# Sitara_Connectors.net
KiCad netlist of a schematic drawn in Altium Designer
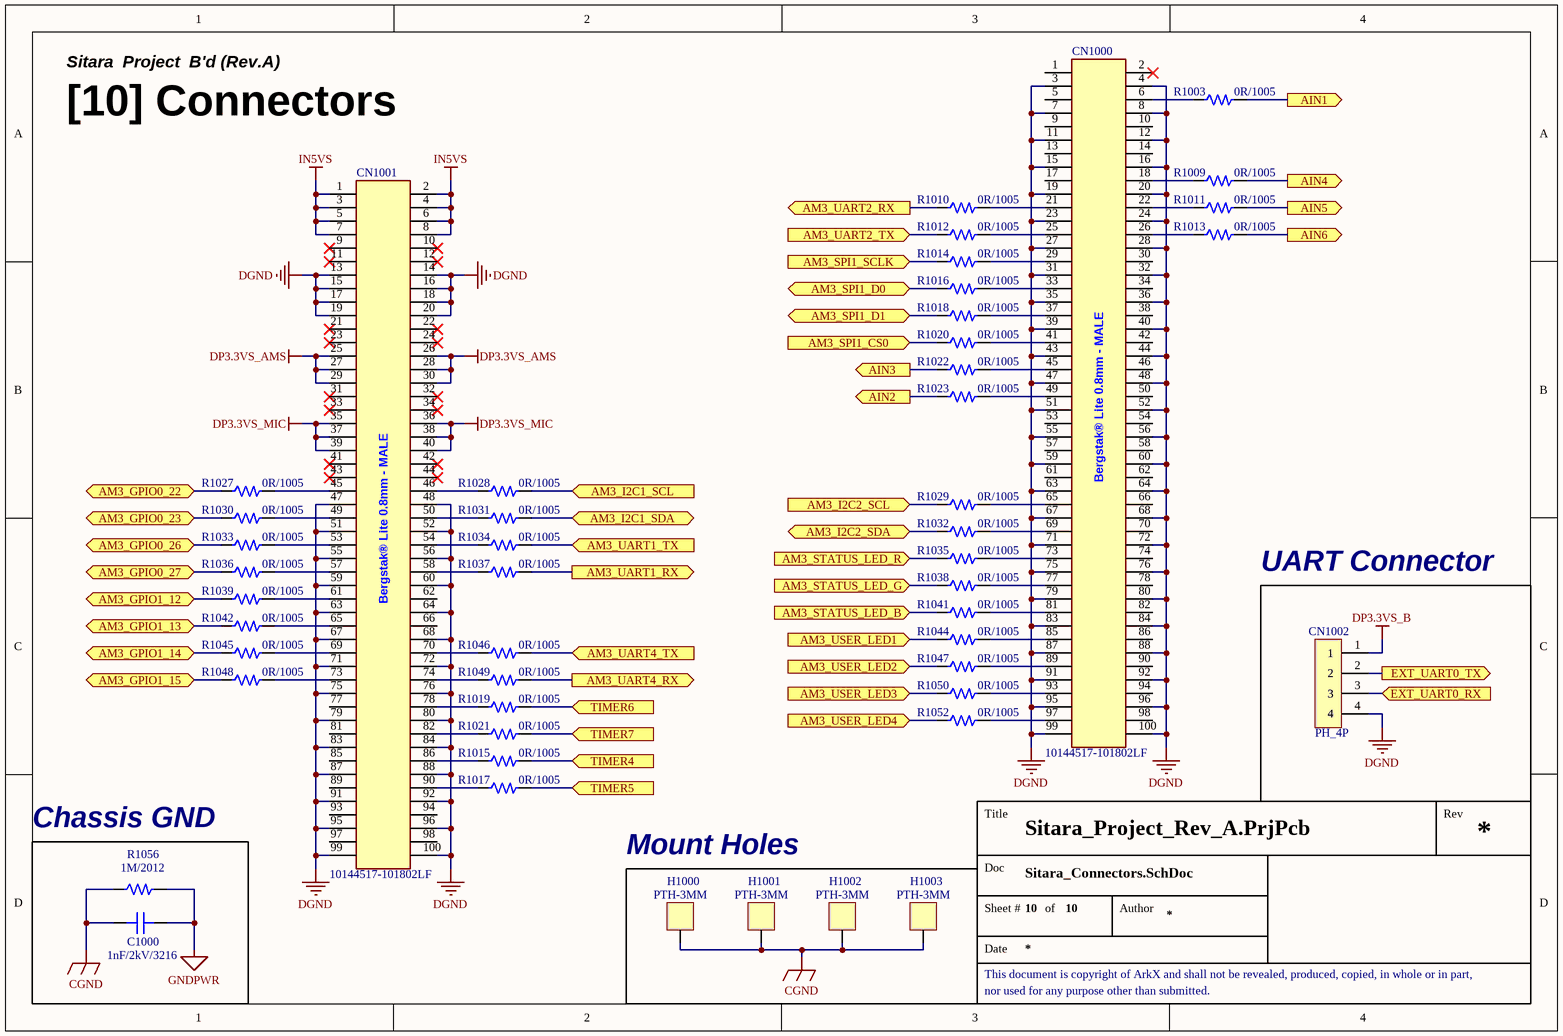
[diagram p0: Sitara_Connectors.SchDoc]

(export (version "E")
  (design (tool "Eeschema 10.0.6"))
  (components
    (comp (ref "C1000")
      (value "1nF/2kV/3216")
      (footprint "CAP 3216 (1206_INCH) - H1.8MM")
      (description "Ceramic CAP_1nF/2kV/3216")
      (fields (field (name "LCSC PART #") "C9196"))
      (libsource (lib "Arkx") (part "CAP_1nF/2kV/3216"))
    )
    (comp (ref "CN1000")
      (value "10144517-101802LF")
      (footprint "CON_BergStak-Lite(0.8mm)_MALE-100P(10144517-101802LF)_HandSolder")
      (libsource (lib "Arkx") (part "CON_BergStak-Lite(0.8mm)_MALE-100P(10144517-101802LF)"))
    )
    (comp (ref "CN1001")
      (value "10144517-101802LF")
      (footprint "CON_BergStak-Lite(0.8mm)_MALE-100P(10144517-101802LF)_HandSolder")
      (libsource (lib "Arkx") (part "CON_BergStak-Lite(0.8mm)_MALE-100P(10144517-101802LF)"))
    )
    (comp (ref "CN1002")
      (value "PH_4P")
      (footprint "CON PIN_HEADER-4PIN(2.54MM)")
      (description "CON_PIN_HEADER_SINGLE-4PIN(2.54MM)")
      (libsource (lib "Arkx") (part "CON_PIN_HEADER_SINGLE-4PIN(2.54MM)"))
    )
    (comp (ref "H1000")
      (value "PTH-3MM")
      (footprint "HOLE PTH-3MM")
      (description "Plated-Through Hole 3mm")
      (libsource (lib "Arkx") (part "HOLE_PTH-3.0MM"))
    )
    (comp (ref "H1001")
      (value "PTH-3MM")
      (footprint "HOLE PTH-3MM")
      (description "Plated-Through Hole 3mm")
      (libsource (lib "Arkx") (part "HOLE_PTH-3.0MM"))
    )
    (comp (ref "H1002")
      (value "PTH-3MM")
      (footprint "HOLE PTH-3MM")
      (description "Plated-Through Hole 3mm")
      (libsource (lib "Arkx") (part "HOLE_PTH-3.0MM"))
    )
    (comp (ref "H1003")
      (value "PTH-3MM")
      (footprint "HOLE PTH-3MM")
      (description "Plated-Through Hole 3mm")
      (libsource (lib "Arkx") (part "HOLE_PTH-3.0MM"))
    )
    (comp (ref "R1003")
      (value "0R/1005")
      (footprint "RES 1005 (0402_inch)")
      (description "RES_0R/1005/62.5mW")
      (fields (field (name "LCSC PART #") "C17168"))
      (libsource (lib "Arkx") (part "RES_0R/1005/62.5mW"))
    )
    (comp (ref "R1009")
      (value "0R/1005")
      (footprint "RES 1005 (0402_inch)")
      (description "RES_0R/1005/62.5mW")
      (fields (field (name "LCSC PART #") "C17168"))
      (libsource (lib "Arkx") (part "RES_0R/1005/62.5mW"))
    )
    (comp (ref "R1010")
      (value "0R/1005")
      (footprint "RES 1005 (0402_inch)")
      (description "RES_0R/1005/62.5mW")
      (fields (field (name "LCSC PART #") "C17168"))
      (libsource (lib "Arkx") (part "RES_0R/1005/62.5mW"))
    )
    (comp (ref "R1011")
      (value "0R/1005")
      (footprint "RES 1005 (0402_inch)")
      (description "RES_0R/1005/62.5mW")
      (fields (field (name "LCSC PART #") "C17168"))
      (libsource (lib "Arkx") (part "RES_0R/1005/62.5mW"))
    )
    (comp (ref "R1012")
      (value "0R/1005")
      (footprint "RES 1005 (0402_inch)")
      (description "RES_0R/1005/62.5mW")
      (fields (field (name "LCSC PART #") "C17168"))
      (libsource (lib "Arkx") (part "RES_0R/1005/62.5mW"))
    )
    (comp (ref "R1013")
      (value "0R/1005")
      (footprint "RES 1005 (0402_inch)")
      (description "RES_0R/1005/62.5mW")
      (fields (field (name "LCSC PART #") "C17168"))
      (libsource (lib "Arkx") (part "RES_0R/1005/62.5mW"))
    )
    (comp (ref "R1014")
      (value "0R/1005")
      (footprint "RES 1005 (0402_inch)")
      (description "RES_0R/1005/62.5mW")
      (fields (field (name "LCSC PART #") "C17168"))
      (libsource (lib "Arkx") (part "RES_0R/1005/62.5mW"))
    )
    (comp (ref "R1015")
      (value "0R/1005")
      (footprint "RES 1005 (0402_inch)")
      (description "RES_0R/1005/62.5mW")
      (fields (field (name "LCSC PART #") "C17168"))
      (libsource (lib "Arkx") (part "RES_0R/1005/62.5mW"))
    )
    (comp (ref "R1016")
      (value "0R/1005")
      (footprint "RES 1005 (0402_inch)")
      (description "RES_0R/1005/62.5mW")
      (fields (field (name "LCSC PART #") "C17168"))
      (libsource (lib "Arkx") (part "RES_0R/1005/62.5mW"))
    )
    (comp (ref "R1017")
      (value "0R/1005")
      (footprint "RES 1005 (0402_inch)")
      (description "RES_0R/1005/62.5mW")
      (fields (field (name "LCSC PART #") "C17168"))
      (libsource (lib "Arkx") (part "RES_0R/1005/62.5mW"))
    )
    (comp (ref "R1018")
      (value "0R/1005")
      (footprint "RES 1005 (0402_inch)")
      (description "RES_0R/1005/62.5mW")
      (fields (field (name "LCSC PART #") "C17168"))
      (libsource (lib "Arkx") (part "RES_0R/1005/62.5mW"))
    )
    (comp (ref "R1019")
      (value "0R/1005")
      (footprint "RES 1005 (0402_inch)")
      (description "RES_0R/1005/62.5mW")
      (fields (field (name "LCSC PART #") "C17168"))
      (libsource (lib "Arkx") (part "RES_0R/1005/62.5mW"))
    )
    (comp (ref "R1020")
      (value "0R/1005")
      (footprint "RES 1005 (0402_inch)")
      (description "RES_0R/1005/62.5mW")
      (fields (field (name "LCSC PART #") "C17168"))
      (libsource (lib "Arkx") (part "RES_0R/1005/62.5mW"))
    )
    (comp (ref "R1021")
      (value "0R/1005")
      (footprint "RES 1005 (0402_inch)")
      (description "RES_0R/1005/62.5mW")
      (fields (field (name "LCSC PART #") "C17168"))
      (libsource (lib "Arkx") (part "RES_0R/1005/62.5mW"))
    )
    (comp (ref "R1022")
      (value "0R/1005")
      (footprint "RES 1005 (0402_inch)")
      (description "RES_0R/1005/62.5mW")
      (fields (field (name "LCSC PART #") "C17168"))
      (libsource (lib "Arkx") (part "RES_0R/1005/62.5mW"))
    )
    (comp (ref "R1023")
      (value "0R/1005")
      (footprint "RES 1005 (0402_inch)")
      (description "RES_0R/1005/62.5mW")
      (fields (field (name "LCSC PART #") "C17168"))
      (libsource (lib "Arkx") (part "RES_0R/1005/62.5mW"))
    )
    (comp (ref "R1027")
      (value "0R/1005")
      (footprint "RES 1005 (0402_inch)")
      (description "RES_0R/1005/62.5mW")
      (fields (field (name "LCSC PART #") "C17168"))
      (libsource (lib "Arkx") (part "RES_0R/1005/62.5mW"))
    )
    (comp (ref "R1028")
      (value "0R/1005")
      (footprint "RES 1005 (0402_inch)")
      (description "RES_0R/1005/62.5mW")
      (fields (field (name "LCSC PART #") "C17168"))
      (libsource (lib "Arkx") (part "RES_0R/1005/62.5mW"))
    )
    (comp (ref "R1029")
      (value "0R/1005")
      (footprint "RES 1005 (0402_inch)")
      (description "RES_0R/1005/62.5mW")
      (fields (field (name "LCSC PART #") "C17168"))
      (libsource (lib "Arkx") (part "RES_0R/1005/62.5mW"))
    )
    (comp (ref "R1030")
      (value "0R/1005")
      (footprint "RES 1005 (0402_inch)")
      (description "RES_0R/1005/62.5mW")
      (fields (field (name "LCSC PART #") "C17168"))
      (libsource (lib "Arkx") (part "RES_0R/1005/62.5mW"))
    )
    (comp (ref "R1031")
      (value "0R/1005")
      (footprint "RES 1005 (0402_inch)")
      (description "RES_0R/1005/62.5mW")
      (fields (field (name "LCSC PART #") "C17168"))
      (libsource (lib "Arkx") (part "RES_0R/1005/62.5mW"))
    )
    (comp (ref "R1032")
      (value "0R/1005")
      (footprint "RES 1005 (0402_inch)")
      (description "RES_0R/1005/62.5mW")
      (fields (field (name "LCSC PART #") "C17168"))
      (libsource (lib "Arkx") (part "RES_0R/1005/62.5mW"))
    )
    (comp (ref "R1033")
      (value "0R/1005")
      (footprint "RES 1005 (0402_inch)")
      (description "RES_0R/1005/62.5mW")
      (fields (field (name "LCSC PART #") "C17168"))
      (libsource (lib "Arkx") (part "RES_0R/1005/62.5mW"))
    )
    (comp (ref "R1034")
      (value "0R/1005")
      (footprint "RES 1005 (0402_inch)")
      (description "RES_0R/1005/62.5mW")
      (fields (field (name "LCSC PART #") "C17168"))
      (libsource (lib "Arkx") (part "RES_0R/1005/62.5mW"))
    )
    (comp (ref "R1035")
      (value "0R/1005")
      (footprint "RES 1005 (0402_inch)")
      (description "RES_0R/1005/62.5mW")
      (fields (field (name "LCSC PART #") "C17168"))
      (libsource (lib "Arkx") (part "RES_0R/1005/62.5mW"))
    )
    (comp (ref "R1036")
      (value "0R/1005")
      (footprint "RES 1005 (0402_inch)")
      (description "RES_0R/1005/62.5mW")
      (fields (field (name "LCSC PART #") "C17168"))
      (libsource (lib "Arkx") (part "RES_0R/1005/62.5mW"))
    )
    (comp (ref "R1037")
      (value "0R/1005")
      (footprint "RES 1005 (0402_inch)")
      (description "RES_0R/1005/62.5mW")
      (fields (field (name "LCSC PART #") "C17168"))
      (libsource (lib "Arkx") (part "RES_0R/1005/62.5mW"))
    )
    (comp (ref "R1038")
      (value "0R/1005")
      (footprint "RES 1005 (0402_inch)")
      (description "RES_0R/1005/62.5mW")
      (fields (field (name "LCSC PART #") "C17168"))
      (libsource (lib "Arkx") (part "RES_0R/1005/62.5mW"))
    )
    (comp (ref "R1039")
      (value "0R/1005")
      (footprint "RES 1005 (0402_inch)")
      (description "RES_0R/1005/62.5mW")
      (fields (field (name "LCSC PART #") "C17168"))
      (libsource (lib "Arkx") (part "RES_0R/1005/62.5mW"))
    )
    (comp (ref "R1041")
      (value "0R/1005")
      (footprint "RES 1005 (0402_inch)")
      (description "RES_0R/1005/62.5mW")
      (fields (field (name "LCSC PART #") "C17168"))
      (libsource (lib "Arkx") (part "RES_0R/1005/62.5mW"))
    )
    (comp (ref "R1042")
      (value "0R/1005")
      (footprint "RES 1005 (0402_inch)")
      (description "RES_0R/1005/62.5mW")
      (fields (field (name "LCSC PART #") "C17168"))
      (libsource (lib "Arkx") (part "RES_0R/1005/62.5mW"))
    )
    (comp (ref "R1044")
      (value "0R/1005")
      (footprint "RES 1005 (0402_inch)")
      (description "RES_0R/1005/62.5mW")
      (fields (field (name "LCSC PART #") "C17168"))
      (libsource (lib "Arkx") (part "RES_0R/1005/62.5mW"))
    )
    (comp (ref "R1045")
      (value "0R/1005")
      (footprint "RES 1005 (0402_inch)")
      (description "RES_0R/1005/62.5mW")
      (fields (field (name "LCSC PART #") "C17168"))
      (libsource (lib "Arkx") (part "RES_0R/1005/62.5mW"))
    )
    (comp (ref "R1046")
      (value "0R/1005")
      (footprint "RES 1005 (0402_inch)")
      (description "RES_0R/1005/62.5mW")
      (fields (field (name "LCSC PART #") "C17168"))
      (libsource (lib "Arkx") (part "RES_0R/1005/62.5mW"))
    )
    (comp (ref "R1047")
      (value "0R/1005")
      (footprint "RES 1005 (0402_inch)")
      (description "RES_0R/1005/62.5mW")
      (fields (field (name "LCSC PART #") "C17168"))
      (libsource (lib "Arkx") (part "RES_0R/1005/62.5mW"))
    )
    (comp (ref "R1048")
      (value "0R/1005")
      (footprint "RES 1005 (0402_inch)")
      (description "RES_0R/1005/62.5mW")
      (fields (field (name "LCSC PART #") "C17168"))
      (libsource (lib "Arkx") (part "RES_0R/1005/62.5mW"))
    )
    (comp (ref "R1049")
      (value "0R/1005")
      (footprint "RES 1005 (0402_inch)")
      (description "RES_0R/1005/62.5mW")
      (fields (field (name "LCSC PART #") "C17168"))
      (libsource (lib "Arkx") (part "RES_0R/1005/62.5mW"))
    )
    (comp (ref "R1050")
      (value "0R/1005")
      (footprint "RES 1005 (0402_inch)")
      (description "RES_0R/1005/62.5mW")
      (fields (field (name "LCSC PART #") "C17168"))
      (libsource (lib "Arkx") (part "RES_0R/1005/62.5mW"))
    )
    (comp (ref "R1052")
      (value "0R/1005")
      (footprint "RES 1005 (0402_inch)")
      (description "RES_0R/1005/62.5mW")
      (fields (field (name "LCSC PART #") "C17168"))
      (libsource (lib "Arkx") (part "RES_0R/1005/62.5mW"))
    )
    (comp (ref "R1056")
      (value "1M/2012")
      (footprint "RES 2012 (0805_inch)")
      (description "RES_1M/2012/0.125W")
      (fields (field (name "LCSC PART #") "C17514"))
      (libsource (lib "Arkx") (part "RES_1M/2012/0.125W"))
    )
  )
  (nets
    (net (code "1") (name "/AIN1") (class "Default")
      (node (ref "R1003") (pin "2") (pinfunction "2_2") (pintype "passive"))
    )
    (net (code "2") (name "/AIN2") (class "Default")
      (node (ref "R1023") (pin "1") (pinfunction "1_1") (pintype "passive"))
    )
    (net (code "3") (name "/AIN3") (class "Default")
      (node (ref "R1022") (pin "1") (pinfunction "1_1") (pintype "passive"))
    )
    (net (code "4") (name "/AIN4") (class "Default")
      (node (ref "R1009") (pin "2") (pinfunction "2_2") (pintype "passive"))
    )
    (net (code "5") (name "/AIN5") (class "Default")
      (node (ref "R1011") (pin "2") (pinfunction "2_2") (pintype "passive"))
    )
    (net (code "6") (name "/AIN6") (class "Default")
      (node (ref "R1013") (pin "2") (pinfunction "2_2") (pintype "passive"))
    )
    (net (code "7") (name "/AM3_GPIO0_22") (class "Default")
      (node (ref "R1027") (pin "1") (pinfunction "1_1") (pintype "passive"))
    )
    (net (code "8") (name "/AM3_GPIO0_23") (class "Default")
      (node (ref "R1030") (pin "1") (pinfunction "1_1") (pintype "passive"))
    )
    (net (code "9") (name "/AM3_GPIO0_26") (class "Default")
      (node (ref "R1033") (pin "1") (pinfunction "1_1") (pintype "passive"))
    )
    (net (code "10") (name "/AM3_GPIO0_27") (class "Default")
      (node (ref "R1036") (pin "1") (pinfunction "1_1") (pintype "passive"))
    )
    (net (code "11") (name "/AM3_GPIO1_12") (class "Default")
      (node (ref "R1039") (pin "1") (pinfunction "1_1") (pintype "passive"))
    )
    (net (code "12") (name "/AM3_GPIO1_13") (class "Default")
      (node (ref "R1042") (pin "1") (pinfunction "1_1") (pintype "passive"))
    )
    (net (code "13") (name "/AM3_GPIO1_14") (class "Default")
      (node (ref "R1045") (pin "1") (pinfunction "1_1") (pintype "passive"))
    )
    (net (code "14") (name "/AM3_GPIO1_15") (class "Default")
      (node (ref "R1048") (pin "1") (pinfunction "1_1") (pintype "passive"))
    )
    (net (code "15") (name "/AM3_I2C1_SCL") (class "Default")
      (node (ref "R1028") (pin "2") (pinfunction "2_2") (pintype "passive"))
    )
    (net (code "16") (name "/AM3_I2C1_SDA") (class "Default")
      (node (ref "R1031") (pin "2") (pinfunction "2_2") (pintype "passive"))
    )
    (net (code "17") (name "/AM3_I2C2_SCL") (class "Default")
      (node (ref "R1029") (pin "1") (pinfunction "1_1") (pintype "passive"))
    )
    (net (code "18") (name "/AM3_I2C2_SDA") (class "Default")
      (node (ref "R1032") (pin "1") (pinfunction "1_1") (pintype "passive"))
    )
    (net (code "19") (name "/AM3_SPI1_CS0") (class "Default")
      (node (ref "R1020") (pin "1") (pinfunction "1_1") (pintype "passive"))
    )
    (net (code "20") (name "/AM3_SPI1_D0") (class "Default")
      (node (ref "R1016") (pin "1") (pinfunction "1_1") (pintype "passive"))
    )
    (net (code "21") (name "/AM3_SPI1_D1") (class "Default")
      (node (ref "R1018") (pin "1") (pinfunction "1_1") (pintype "passive"))
    )
    (net (code "22") (name "/AM3_SPI1_SCLK") (class "Default")
      (node (ref "R1014") (pin "1") (pinfunction "1_1") (pintype "passive"))
    )
    (net (code "23") (name "/AM3_STATUS_LED_B") (class "Default")
      (node (ref "R1041") (pin "1") (pinfunction "1_1") (pintype "passive"))
    )
    (net (code "24") (name "/AM3_STATUS_LED_G") (class "Default")
      (node (ref "R1038") (pin "1") (pinfunction "1_1") (pintype "passive"))
    )
    (net (code "25") (name "/AM3_STATUS_LED_R") (class "Default")
      (node (ref "R1035") (pin "1") (pinfunction "1_1") (pintype "passive"))
    )
    (net (code "26") (name "/AM3_UART1_RX") (class "Default")
      (node (ref "R1037") (pin "2") (pinfunction "2_2") (pintype "passive"))
    )
    (net (code "27") (name "/AM3_UART1_TX") (class "Default")
      (node (ref "R1034") (pin "2") (pinfunction "2_2") (pintype "passive"))
    )
    (net (code "28") (name "/AM3_UART2_RX") (class "Default")
      (node (ref "R1010") (pin "1") (pinfunction "1_1") (pintype "passive"))
    )
    (net (code "29") (name "/AM3_UART2_TX") (class "Default")
      (node (ref "R1012") (pin "1") (pinfunction "1_1") (pintype "passive"))
    )
    (net (code "30") (name "/AM3_UART4_RX") (class "Default")
      (node (ref "R1049") (pin "2") (pinfunction "2_2") (pintype "passive"))
    )
    (net (code "31") (name "/AM3_UART4_TX") (class "Default")
      (node (ref "R1046") (pin "2") (pinfunction "2_2") (pintype "passive"))
    )
    (net (code "32") (name "/AM3_USER_LED1") (class "Default")
      (node (ref "R1044") (pin "1") (pinfunction "1_1") (pintype "passive"))
    )
    (net (code "33") (name "/AM3_USER_LED2") (class "Default")
      (node (ref "R1047") (pin "1") (pinfunction "1_1") (pintype "passive"))
    )
    (net (code "34") (name "/AM3_USER_LED3") (class "Default")
      (node (ref "R1050") (pin "1") (pinfunction "1_1") (pintype "passive"))
    )
    (net (code "35") (name "/AM3_USER_LED4") (class "Default")
      (node (ref "R1052") (pin "1") (pinfunction "1_1") (pintype "passive"))
    )
    (net (code "36") (name "/EXT_UART0_RX") (class "Default")
      (node (ref "CN1002") (pin "3") (pinfunction "3_3") (pintype "passive"))
    )
    (net (code "37") (name "/EXT_UART0_TX") (class "Default")
      (node (ref "CN1002") (pin "2") (pinfunction "2_2") (pintype "passive"))
    )
    (net (code "38") (name "/TIMER4") (class "Default")
      (node (ref "R1015") (pin "2") (pinfunction "2_2") (pintype "passive"))
    )
    (net (code "39") (name "/TIMER5") (class "Default")
      (node (ref "R1017") (pin "2") (pinfunction "2_2") (pintype "passive"))
    )
    (net (code "40") (name "/TIMER6") (class "Default")
      (node (ref "R1019") (pin "2") (pinfunction "2_2") (pintype "passive"))
    )
    (net (code "41") (name "/TIMER7") (class "Default")
      (node (ref "R1021") (pin "2") (pinfunction "2_2") (pintype "passive"))
    )
    (net (code "42") (name "CGND") (class "Default")
      (node (ref "C1000") (pin "1") (pinfunction "1_1") (pintype "passive"))
      (node (ref "H1000") (pin "1") (pinfunction "1_1") (pintype "passive"))
      (node (ref "H1001") (pin "1") (pinfunction "1_1") (pintype "passive"))
      (node (ref "H1002") (pin "1") (pinfunction "1_1") (pintype "passive"))
      (node (ref "H1003") (pin "1") (pinfunction "1_1") (pintype "passive"))
      (node (ref "R1056") (pin "1") (pinfunction "1_1") (pintype "passive"))
    )
    (net (code "43") (name "DGND") (class "Default")
      (node (ref "CN1000") (pin "100") (pinfunction "100_100") (pintype "passive"))
      (node (ref "CN1000") (pin "11") (pinfunction "11_11") (pintype "passive"))
      (node (ref "CN1000") (pin "12") (pinfunction "12_12") (pintype "passive"))
      (node (ref "CN1000") (pin "15") (pinfunction "15_15") (pintype "passive"))
      (node (ref "CN1000") (pin "16") (pinfunction "16_16") (pintype "passive"))
      (node (ref "CN1000") (pin "19") (pinfunction "19_19") (pintype "passive"))
      (node (ref "CN1000") (pin "20") (pinfunction "20_20") (pintype "passive"))
      (node (ref "CN1000") (pin "23") (pinfunction "23_23") (pintype "passive"))
      (node (ref "CN1000") (pin "24") (pinfunction "24_24") (pintype "passive"))
      (node (ref "CN1000") (pin "27") (pinfunction "27_27") (pintype "passive"))
      (node (ref "CN1000") (pin "28") (pinfunction "28_28") (pintype "passive"))
      (node (ref "CN1000") (pin "3") (pinfunction "3_3") (pintype "passive"))
      (node (ref "CN1000") (pin "31") (pinfunction "31_31") (pintype "passive"))
      (node (ref "CN1000") (pin "32") (pinfunction "32_32") (pintype "passive"))
      (node (ref "CN1000") (pin "35") (pinfunction "35_35") (pintype "passive"))
      (node (ref "CN1000") (pin "36") (pinfunction "36_36") (pintype "passive"))
      (node (ref "CN1000") (pin "39") (pinfunction "39_39") (pintype "passive"))
      (node (ref "CN1000") (pin "4") (pinfunction "4_4") (pintype "passive"))
      (node (ref "CN1000") (pin "40") (pinfunction "40_40") (pintype "passive"))
      (node (ref "CN1000") (pin "43") (pinfunction "43_43") (pintype "passive"))
      (node (ref "CN1000") (pin "44") (pinfunction "44_44") (pintype "passive"))
      (node (ref "CN1000") (pin "47") (pinfunction "47_47") (pintype "passive"))
      (node (ref "CN1000") (pin "48") (pinfunction "48_48") (pintype "passive"))
      (node (ref "CN1000") (pin "51") (pinfunction "51_51") (pintype "passive"))
      (node (ref "CN1000") (pin "52") (pinfunction "52_52") (pintype "passive"))
      (node (ref "CN1000") (pin "55") (pinfunction "55_55") (pintype "passive"))
      (node (ref "CN1000") (pin "56") (pinfunction "56_56") (pintype "passive"))
      (node (ref "CN1000") (pin "59") (pinfunction "59_59") (pintype "passive"))
      (node (ref "CN1000") (pin "60") (pinfunction "60_60") (pintype "passive"))
      (node (ref "CN1000") (pin "63") (pinfunction "63_63") (pintype "passive"))
      (node (ref "CN1000") (pin "64") (pinfunction "64_64") (pintype "passive"))
      (node (ref "CN1000") (pin "67") (pinfunction "67_67") (pintype "passive"))
      (node (ref "CN1000") (pin "68") (pinfunction "68_68") (pintype "passive"))
      (node (ref "CN1000") (pin "7") (pinfunction "7_7") (pintype "passive"))
      (node (ref "CN1000") (pin "71") (pinfunction "71_71") (pintype "passive"))
      (node (ref "CN1000") (pin "72") (pinfunction "72_72") (pintype "passive"))
      (node (ref "CN1000") (pin "75") (pinfunction "75_75") (pintype "passive"))
      (node (ref "CN1000") (pin "76") (pinfunction "76_76") (pintype "passive"))
      (node (ref "CN1000") (pin "79") (pinfunction "79_79") (pintype "passive"))
      (node (ref "CN1000") (pin "8") (pinfunction "8_8") (pintype "passive"))
      (node (ref "CN1000") (pin "80") (pinfunction "80_80") (pintype "passive"))
      (node (ref "CN1000") (pin "83") (pinfunction "83_83") (pintype "passive"))
      (node (ref "CN1000") (pin "84") (pinfunction "84_84") (pintype "passive"))
      (node (ref "CN1000") (pin "87") (pinfunction "87_87") (pintype "passive"))
      (node (ref "CN1000") (pin "88") (pinfunction "88_88") (pintype "passive"))
      (node (ref "CN1000") (pin "91") (pinfunction "91_91") (pintype "passive"))
      (node (ref "CN1000") (pin "92") (pinfunction "92_92") (pintype "passive"))
      (node (ref "CN1000") (pin "95") (pinfunction "95_95") (pintype "passive"))
      (node (ref "CN1000") (pin "96") (pinfunction "96_96") (pintype "passive"))
      (node (ref "CN1000") (pin "99") (pinfunction "99_99") (pintype "passive"))
      (node (ref "CN1001") (pin "100") (pinfunction "100_100") (pintype "passive"))
      (node (ref "CN1001") (pin "13") (pinfunction "13_13") (pintype "passive"))
      (node (ref "CN1001") (pin "14") (pinfunction "14_14") (pintype "passive"))
      (node (ref "CN1001") (pin "15") (pinfunction "15_15") (pintype "passive"))
      (node (ref "CN1001") (pin "16") (pinfunction "16_16") (pintype "passive"))
      (node (ref "CN1001") (pin "17") (pinfunction "17_17") (pintype "passive"))
      (node (ref "CN1001") (pin "18") (pinfunction "18_18") (pintype "passive"))
      (node (ref "CN1001") (pin "19") (pinfunction "19_19") (pintype "passive"))
      (node (ref "CN1001") (pin "20") (pinfunction "20_20") (pintype "passive"))
      (node (ref "CN1001") (pin "47") (pinfunction "47_47") (pintype "passive"))
      (node (ref "CN1001") (pin "48") (pinfunction "48_48") (pintype "passive"))
      (node (ref "CN1001") (pin "51") (pinfunction "51_51") (pintype "passive"))
      (node (ref "CN1001") (pin "52") (pinfunction "52_52") (pintype "passive"))
      (node (ref "CN1001") (pin "55") (pinfunction "55_55") (pintype "passive"))
      (node (ref "CN1001") (pin "56") (pinfunction "56_56") (pintype "passive"))
      (node (ref "CN1001") (pin "59") (pinfunction "59_59") (pintype "passive"))
      (node (ref "CN1001") (pin "60") (pinfunction "60_60") (pintype "passive"))
      (node (ref "CN1001") (pin "63") (pinfunction "63_63") (pintype "passive"))
      (node (ref "CN1001") (pin "64") (pinfunction "64_64") (pintype "passive"))
      (node (ref "CN1001") (pin "67") (pinfunction "67_67") (pintype "passive"))
      (node (ref "CN1001") (pin "68") (pinfunction "68_68") (pintype "passive"))
      (node (ref "CN1001") (pin "71") (pinfunction "71_71") (pintype "passive"))
      (node (ref "CN1001") (pin "72") (pinfunction "72_72") (pintype "passive"))
      (node (ref "CN1001") (pin "75") (pinfunction "75_75") (pintype "passive"))
      (node (ref "CN1001") (pin "76") (pinfunction "76_76") (pintype "passive"))
      (node (ref "CN1001") (pin "79") (pinfunction "79_79") (pintype "passive"))
      (node (ref "CN1001") (pin "80") (pinfunction "80_80") (pintype "passive"))
      (node (ref "CN1001") (pin "83") (pinfunction "83_83") (pintype "passive"))
      (node (ref "CN1001") (pin "84") (pinfunction "84_84") (pintype "passive"))
      (node (ref "CN1001") (pin "87") (pinfunction "87_87") (pintype "passive"))
      (node (ref "CN1001") (pin "88") (pinfunction "88_88") (pintype "passive"))
      (node (ref "CN1001") (pin "91") (pinfunction "91_91") (pintype "passive"))
      (node (ref "CN1001") (pin "92") (pinfunction "92_92") (pintype "passive"))
      (node (ref "CN1001") (pin "95") (pinfunction "95_95") (pintype "passive"))
      (node (ref "CN1001") (pin "96") (pinfunction "96_96") (pintype "passive"))
      (node (ref "CN1001") (pin "99") (pinfunction "99_99") (pintype "passive"))
      (node (ref "CN1002") (pin "4") (pinfunction "4_4") (pintype "passive"))
    )
    (net (code "44") (name "DP3.3VS_AMS") (class "Default")
      (node (ref "CN1001") (pin "25") (pinfunction "25_25") (pintype "passive"))
      (node (ref "CN1001") (pin "26") (pinfunction "26_26") (pintype "passive"))
      (node (ref "CN1001") (pin "27") (pinfunction "27_27") (pintype "passive"))
      (node (ref "CN1001") (pin "28") (pinfunction "28_28") (pintype "passive"))
      (node (ref "CN1001") (pin "29") (pinfunction "29_29") (pintype "passive"))
      (node (ref "CN1001") (pin "30") (pinfunction "30_30") (pintype "passive"))
    )
    (net (code "45") (name "DP3.3VS_B") (class "Default")
      (node (ref "CN1002") (pin "1") (pinfunction "1_1") (pintype "passive"))
    )
    (net (code "46") (name "DP3.3VS_MIC") (class "Default")
      (node (ref "CN1001") (pin "35") (pinfunction "35_35") (pintype "passive"))
      (node (ref "CN1001") (pin "36") (pinfunction "36_36") (pintype "passive"))
      (node (ref "CN1001") (pin "37") (pinfunction "37_37") (pintype "passive"))
      (node (ref "CN1001") (pin "38") (pinfunction "38_38") (pintype "passive"))
      (node (ref "CN1001") (pin "39") (pinfunction "39_39") (pintype "passive"))
      (node (ref "CN1001") (pin "40") (pinfunction "40_40") (pintype "passive"))
    )
    (net (code "47") (name "GNDPWR") (class "Default")
      (node (ref "C1000") (pin "2") (pinfunction "2_2") (pintype "passive"))
      (node (ref "R1056") (pin "2") (pinfunction "2_2") (pintype "passive"))
    )
    (net (code "48") (name "IN5VS") (class "Default")
      (node (ref "CN1001") (pin "1") (pinfunction "1_1") (pintype "passive"))
      (node (ref "CN1001") (pin "2") (pinfunction "2_2") (pintype "passive"))
      (node (ref "CN1001") (pin "3") (pinfunction "3_3") (pintype "passive"))
      (node (ref "CN1001") (pin "4") (pinfunction "4_4") (pintype "passive"))
      (node (ref "CN1001") (pin "5") (pinfunction "5_5") (pintype "passive"))
      (node (ref "CN1001") (pin "6") (pinfunction "6_6") (pintype "passive"))
      (node (ref "CN1001") (pin "7") (pinfunction "7_7") (pintype "passive"))
      (node (ref "CN1001") (pin "8") (pinfunction "8_8") (pintype "passive"))
    )
    (net (code "49") (name "Net-(CN1000-Pad6)") (class "Default")
      (node (ref "CN1000") (pin "6") (pinfunction "6_6") (pintype "passive"))
      (node (ref "R1003") (pin "1") (pinfunction "1_1") (pintype "passive"))
    )
    (net (code "50") (name "Net-(CN1000-Pad18)") (class "Default")
      (node (ref "CN1000") (pin "18") (pinfunction "18_18") (pintype "passive"))
      (node (ref "R1009") (pin "1") (pinfunction "1_1") (pintype "passive"))
    )
    (net (code "51") (name "Net-(CN1000-Pad21)") (class "Default")
      (node (ref "CN1000") (pin "21") (pinfunction "21_21") (pintype "passive"))
      (node (ref "R1010") (pin "2") (pinfunction "2_2") (pintype "passive"))
    )
    (net (code "52") (name "Net-(CN1000-Pad22)") (class "Default")
      (node (ref "CN1000") (pin "22") (pinfunction "22_22") (pintype "passive"))
      (node (ref "R1011") (pin "1") (pinfunction "1_1") (pintype "passive"))
    )
    (net (code "53") (name "Net-(CN1000-Pad25)") (class "Default")
      (node (ref "CN1000") (pin "25") (pinfunction "25_25") (pintype "passive"))
      (node (ref "R1012") (pin "2") (pinfunction "2_2") (pintype "passive"))
    )
    (net (code "54") (name "Net-(CN1000-Pad26)") (class "Default")
      (node (ref "CN1000") (pin "26") (pinfunction "26_26") (pintype "passive"))
      (node (ref "R1013") (pin "1") (pinfunction "1_1") (pintype "passive"))
    )
    (net (code "55") (name "Net-(CN1000-Pad29)") (class "Default")
      (node (ref "CN1000") (pin "29") (pinfunction "29_29") (pintype "passive"))
      (node (ref "R1014") (pin "2") (pinfunction "2_2") (pintype "passive"))
    )
    (net (code "56") (name "Net-(CN1000-Pad33)") (class "Default")
      (node (ref "CN1000") (pin "33") (pinfunction "33_33") (pintype "passive"))
      (node (ref "R1016") (pin "2") (pinfunction "2_2") (pintype "passive"))
    )
    (net (code "57") (name "Net-(CN1000-Pad37)") (class "Default")
      (node (ref "CN1000") (pin "37") (pinfunction "37_37") (pintype "passive"))
      (node (ref "R1018") (pin "2") (pinfunction "2_2") (pintype "passive"))
    )
    (net (code "58") (name "Net-(CN1000-Pad41)") (class "Default")
      (node (ref "CN1000") (pin "41") (pinfunction "41_41") (pintype "passive"))
      (node (ref "R1020") (pin "2") (pinfunction "2_2") (pintype "passive"))
    )
    (net (code "59") (name "Net-(CN1000-Pad45)") (class "Default")
      (node (ref "CN1000") (pin "45") (pinfunction "45_45") (pintype "passive"))
      (node (ref "R1022") (pin "2") (pinfunction "2_2") (pintype "passive"))
    )
    (net (code "60") (name "Net-(CN1000-Pad49)") (class "Default")
      (node (ref "CN1000") (pin "49") (pinfunction "49_49") (pintype "passive"))
      (node (ref "R1023") (pin "2") (pinfunction "2_2") (pintype "passive"))
    )
    (net (code "61") (name "Net-(CN1000-Pad65)") (class "Default")
      (node (ref "CN1000") (pin "65") (pinfunction "65_65") (pintype "passive"))
      (node (ref "R1029") (pin "2") (pinfunction "2_2") (pintype "passive"))
    )
    (net (code "62") (name "Net-(CN1000-Pad69)") (class "Default")
      (node (ref "CN1000") (pin "69") (pinfunction "69_69") (pintype "passive"))
      (node (ref "R1032") (pin "2") (pinfunction "2_2") (pintype "passive"))
    )
    (net (code "63") (name "Net-(CN1000-Pad73)") (class "Default")
      (node (ref "CN1000") (pin "73") (pinfunction "73_73") (pintype "passive"))
      (node (ref "R1035") (pin "2") (pinfunction "2_2") (pintype "passive"))
    )
    (net (code "64") (name "Net-(CN1000-Pad77)") (class "Default")
      (node (ref "CN1000") (pin "77") (pinfunction "77_77") (pintype "passive"))
      (node (ref "R1038") (pin "2") (pinfunction "2_2") (pintype "passive"))
    )
    (net (code "65") (name "Net-(CN1000-Pad81)") (class "Default")
      (node (ref "CN1000") (pin "81") (pinfunction "81_81") (pintype "passive"))
      (node (ref "R1041") (pin "2") (pinfunction "2_2") (pintype "passive"))
    )
    (net (code "66") (name "Net-(CN1000-Pad85)") (class "Default")
      (node (ref "CN1000") (pin "85") (pinfunction "85_85") (pintype "passive"))
      (node (ref "R1044") (pin "2") (pinfunction "2_2") (pintype "passive"))
    )
    (net (code "67") (name "Net-(CN1000-Pad89)") (class "Default")
      (node (ref "CN1000") (pin "89") (pinfunction "89_89") (pintype "passive"))
      (node (ref "R1047") (pin "2") (pinfunction "2_2") (pintype "passive"))
    )
    (net (code "68") (name "Net-(CN1000-Pad93)") (class "Default")
      (node (ref "CN1000") (pin "93") (pinfunction "93_93") (pintype "passive"))
      (node (ref "R1050") (pin "2") (pinfunction "2_2") (pintype "passive"))
    )
    (net (code "69") (name "Net-(CN1000-Pad97)") (class "Default")
      (node (ref "CN1000") (pin "97") (pinfunction "97_97") (pintype "passive"))
      (node (ref "R1052") (pin "2") (pinfunction "2_2") (pintype "passive"))
    )
    (net (code "70") (name "Net-(CN1001-Pad45)") (class "Default")
      (node (ref "CN1001") (pin "45") (pinfunction "45_45") (pintype "passive"))
      (node (ref "R1027") (pin "2") (pinfunction "2_2") (pintype "passive"))
    )
    (net (code "71") (name "Net-(CN1001-Pad46)") (class "Default")
      (node (ref "CN1001") (pin "46") (pinfunction "46_46") (pintype "passive"))
      (node (ref "R1028") (pin "1") (pinfunction "1_1") (pintype "passive"))
    )
    (net (code "72") (name "Net-(CN1001-Pad49)") (class "Default")
      (node (ref "CN1001") (pin "49") (pinfunction "49_49") (pintype "passive"))
      (node (ref "R1030") (pin "2") (pinfunction "2_2") (pintype "passive"))
    )
    (net (code "73") (name "Net-(CN1001-Pad50)") (class "Default")
      (node (ref "CN1001") (pin "50") (pinfunction "50_50") (pintype "passive"))
      (node (ref "R1031") (pin "1") (pinfunction "1_1") (pintype "passive"))
    )
    (net (code "74") (name "Net-(CN1001-Pad53)") (class "Default")
      (node (ref "CN1001") (pin "53") (pinfunction "53_53") (pintype "passive"))
      (node (ref "R1033") (pin "2") (pinfunction "2_2") (pintype "passive"))
    )
    (net (code "75") (name "Net-(CN1001-Pad54)") (class "Default")
      (node (ref "CN1001") (pin "54") (pinfunction "54_54") (pintype "passive"))
      (node (ref "R1034") (pin "1") (pinfunction "1_1") (pintype "passive"))
    )
    (net (code "76") (name "Net-(CN1001-Pad57)") (class "Default")
      (node (ref "CN1001") (pin "57") (pinfunction "57_57") (pintype "passive"))
      (node (ref "R1036") (pin "2") (pinfunction "2_2") (pintype "passive"))
    )
    (net (code "77") (name "Net-(CN1001-Pad58)") (class "Default")
      (node (ref "CN1001") (pin "58") (pinfunction "58_58") (pintype "passive"))
      (node (ref "R1037") (pin "1") (pinfunction "1_1") (pintype "passive"))
    )
    (net (code "78") (name "Net-(CN1001-Pad61)") (class "Default")
      (node (ref "CN1001") (pin "61") (pinfunction "61_61") (pintype "passive"))
      (node (ref "R1039") (pin "2") (pinfunction "2_2") (pintype "passive"))
    )
    (net (code "79") (name "Net-(CN1001-Pad65)") (class "Default")
      (node (ref "CN1001") (pin "65") (pinfunction "65_65") (pintype "passive"))
      (node (ref "R1042") (pin "2") (pinfunction "2_2") (pintype "passive"))
    )
    (net (code "80") (name "Net-(CN1001-Pad69)") (class "Default")
      (node (ref "CN1001") (pin "69") (pinfunction "69_69") (pintype "passive"))
      (node (ref "R1045") (pin "2") (pinfunction "2_2") (pintype "passive"))
    )
    (net (code "81") (name "Net-(CN1001-Pad70)") (class "Default")
      (node (ref "CN1001") (pin "70") (pinfunction "70_70") (pintype "passive"))
      (node (ref "R1046") (pin "1") (pinfunction "1_1") (pintype "passive"))
    )
    (net (code "82") (name "Net-(CN1001-Pad73)") (class "Default")
      (node (ref "CN1001") (pin "73") (pinfunction "73_73") (pintype "passive"))
      (node (ref "R1048") (pin "2") (pinfunction "2_2") (pintype "passive"))
    )
    (net (code "83") (name "Net-(CN1001-Pad74)") (class "Default")
      (node (ref "CN1001") (pin "74") (pinfunction "74_74") (pintype "passive"))
      (node (ref "R1049") (pin "1") (pinfunction "1_1") (pintype "passive"))
    )
    (net (code "84") (name "Net-(CN1001-Pad78)") (class "Default")
      (node (ref "CN1001") (pin "78") (pinfunction "78_78") (pintype "passive"))
      (node (ref "R1019") (pin "1") (pinfunction "1_1") (pintype "passive"))
    )
    (net (code "85") (name "Net-(CN1001-Pad82)") (class "Default")
      (node (ref "CN1001") (pin "82") (pinfunction "82_82") (pintype "passive"))
      (node (ref "R1021") (pin "1") (pinfunction "1_1") (pintype "passive"))
    )
    (net (code "86") (name "Net-(CN1001-Pad86)") (class "Default")
      (node (ref "CN1001") (pin "86") (pinfunction "86_86") (pintype "passive"))
      (node (ref "R1015") (pin "1") (pinfunction "1_1") (pintype "passive"))
    )
    (net (code "87") (name "Net-(CN1001-Pad90)") (class "Default")
      (node (ref "CN1001") (pin "90") (pinfunction "90_90") (pintype "passive"))
      (node (ref "R1017") (pin "1") (pinfunction "1_1") (pintype "passive"))
    )
    (net (code "88") (name "unconnected-(CN1000-Pad1)") (class "Default")
      (node (ref "CN1000") (pin "1") (pinfunction "1_1") (pintype "passive"))
    )
    (net (code "89") (name "unconnected-(CN1000-Pad2)") (class "Default")
      (node (ref "CN1000") (pin "2") (pinfunction "2_2") (pintype "passive+no_connect"))
    )
    (net (code "90") (name "unconnected-(CN1000-Pad5)") (class "Default")
      (node (ref "CN1000") (pin "5") (pinfunction "5_5") (pintype "passive"))
    )
    (net (code "91") (name "unconnected-(CN1000-Pad9)") (class "Default")
      (node (ref "CN1000") (pin "9") (pinfunction "9_9") (pintype "passive"))
    )
    (net (code "92") (name "unconnected-(CN1000-Pad10)") (class "Default")
      (node (ref "CN1000") (pin "10") (pinfunction "10_10") (pintype "passive"))
    )
    (net (code "93") (name "unconnected-(CN1000-Pad13)") (class "Default")
      (node (ref "CN1000") (pin "13") (pinfunction "13_13") (pintype "passive"))
    )
    (net (code "94") (name "unconnected-(CN1000-Pad14)") (class "Default")
      (node (ref "CN1000") (pin "14") (pinfunction "14_14") (pintype "passive"))
    )
    (net (code "95") (name "unconnected-(CN1000-Pad17)") (class "Default")
      (node (ref "CN1000") (pin "17") (pinfunction "17_17") (pintype "passive"))
    )
    (net (code "96") (name "unconnected-(CN1000-Pad30)") (class "Default")
      (node (ref "CN1000") (pin "30") (pinfunction "30_30") (pintype "passive"))
    )
    (net (code "97") (name "unconnected-(CN1000-Pad34)") (class "Default")
      (node (ref "CN1000") (pin "34") (pinfunction "34_34") (pintype "passive"))
    )
    (net (code "98") (name "unconnected-(CN1000-Pad38)") (class "Default")
      (node (ref "CN1000") (pin "38") (pinfunction "38_38") (pintype "passive"))
    )
    (net (code "99") (name "unconnected-(CN1000-Pad42)") (class "Default")
      (node (ref "CN1000") (pin "42") (pinfunction "42_42") (pintype "passive"))
    )
    (net (code "100") (name "unconnected-(CN1000-Pad46)") (class "Default")
      (node (ref "CN1000") (pin "46") (pinfunction "46_46") (pintype "passive"))
    )
    (net (code "101") (name "unconnected-(CN1000-Pad50)") (class "Default")
      (node (ref "CN1000") (pin "50") (pinfunction "50_50") (pintype "passive"))
    )
    (net (code "102") (name "unconnected-(CN1000-Pad53)") (class "Default")
      (node (ref "CN1000") (pin "53") (pinfunction "53_53") (pintype "passive"))
    )
    (net (code "103") (name "unconnected-(CN1000-Pad54)") (class "Default")
      (node (ref "CN1000") (pin "54") (pinfunction "54_54") (pintype "passive"))
    )
    (net (code "104") (name "unconnected-(CN1000-Pad57)") (class "Default")
      (node (ref "CN1000") (pin "57") (pinfunction "57_57") (pintype "passive"))
    )
    (net (code "105") (name "unconnected-(CN1000-Pad58)") (class "Default")
      (node (ref "CN1000") (pin "58") (pinfunction "58_58") (pintype "passive"))
    )
    (net (code "106") (name "unconnected-(CN1000-Pad61)") (class "Default")
      (node (ref "CN1000") (pin "61") (pinfunction "61_61") (pintype "passive"))
    )
    (net (code "107") (name "unconnected-(CN1000-Pad62)") (class "Default")
      (node (ref "CN1000") (pin "62") (pinfunction "62_62") (pintype "passive"))
    )
    (net (code "108") (name "unconnected-(CN1000-Pad66)") (class "Default")
      (node (ref "CN1000") (pin "66") (pinfunction "66_66") (pintype "passive"))
    )
    (net (code "109") (name "unconnected-(CN1000-Pad70)") (class "Default")
      (node (ref "CN1000") (pin "70") (pinfunction "70_70") (pintype "passive"))
    )
    (net (code "110") (name "unconnected-(CN1000-Pad74)") (class "Default")
      (node (ref "CN1000") (pin "74") (pinfunction "74_74") (pintype "passive"))
    )
    (net (code "111") (name "unconnected-(CN1000-Pad78)") (class "Default")
      (node (ref "CN1000") (pin "78") (pinfunction "78_78") (pintype "passive"))
    )
    (net (code "112") (name "unconnected-(CN1000-Pad82)") (class "Default")
      (node (ref "CN1000") (pin "82") (pinfunction "82_82") (pintype "passive"))
    )
    (net (code "113") (name "unconnected-(CN1000-Pad86)") (class "Default")
      (node (ref "CN1000") (pin "86") (pinfunction "86_86") (pintype "passive"))
    )
    (net (code "114") (name "unconnected-(CN1000-Pad90)") (class "Default")
      (node (ref "CN1000") (pin "90") (pinfunction "90_90") (pintype "passive"))
    )
    (net (code "115") (name "unconnected-(CN1000-Pad94)") (class "Default")
      (node (ref "CN1000") (pin "94") (pinfunction "94_94") (pintype "passive"))
    )
    (net (code "116") (name "unconnected-(CN1000-Pad98)") (class "Default")
      (node (ref "CN1000") (pin "98") (pinfunction "98_98") (pintype "passive"))
    )
    (net (code "117") (name "unconnected-(CN1001-Pad9)") (class "Default")
      (node (ref "CN1001") (pin "9") (pinfunction "9_9") (pintype "passive+no_connect"))
    )
    (net (code "118") (name "unconnected-(CN1001-Pad10)") (class "Default")
      (node (ref "CN1001") (pin "10") (pinfunction "10_10") (pintype "passive+no_connect"))
    )
    (net (code "119") (name "unconnected-(CN1001-Pad11)") (class "Default")
      (node (ref "CN1001") (pin "11") (pinfunction "11_11") (pintype "passive+no_connect"))
    )
    (net (code "120") (name "unconnected-(CN1001-Pad12)") (class "Default")
      (node (ref "CN1001") (pin "12") (pinfunction "12_12") (pintype "passive+no_connect"))
    )
    (net (code "121") (name "unconnected-(CN1001-Pad21)") (class "Default")
      (node (ref "CN1001") (pin "21") (pinfunction "21_21") (pintype "passive+no_connect"))
    )
    (net (code "122") (name "unconnected-(CN1001-Pad22)") (class "Default")
      (node (ref "CN1001") (pin "22") (pinfunction "22_22") (pintype "passive+no_connect"))
    )
    (net (code "123") (name "unconnected-(CN1001-Pad23)") (class "Default")
      (node (ref "CN1001") (pin "23") (pinfunction "23_23") (pintype "passive+no_connect"))
    )
    (net (code "124") (name "unconnected-(CN1001-Pad24)") (class "Default")
      (node (ref "CN1001") (pin "24") (pinfunction "24_24") (pintype "passive+no_connect"))
    )
    (net (code "125") (name "unconnected-(CN1001-Pad31)") (class "Default")
      (node (ref "CN1001") (pin "31") (pinfunction "31_31") (pintype "passive+no_connect"))
    )
    (net (code "126") (name "unconnected-(CN1001-Pad32)") (class "Default")
      (node (ref "CN1001") (pin "32") (pinfunction "32_32") (pintype "passive+no_connect"))
    )
    (net (code "127") (name "unconnected-(CN1001-Pad33)") (class "Default")
      (node (ref "CN1001") (pin "33") (pinfunction "33_33") (pintype "passive+no_connect"))
    )
    (net (code "128") (name "unconnected-(CN1001-Pad34)") (class "Default")
      (node (ref "CN1001") (pin "34") (pinfunction "34_34") (pintype "passive+no_connect"))
    )
    (net (code "129") (name "unconnected-(CN1001-Pad41)") (class "Default")
      (node (ref "CN1001") (pin "41") (pinfunction "41_41") (pintype "passive+no_connect"))
    )
    (net (code "130") (name "unconnected-(CN1001-Pad42)") (class "Default")
      (node (ref "CN1001") (pin "42") (pinfunction "42_42") (pintype "passive+no_connect"))
    )
    (net (code "131") (name "unconnected-(CN1001-Pad43)") (class "Default")
      (node (ref "CN1001") (pin "43") (pinfunction "43_43") (pintype "passive+no_connect"))
    )
    (net (code "132") (name "unconnected-(CN1001-Pad44)") (class "Default")
      (node (ref "CN1001") (pin "44") (pinfunction "44_44") (pintype "passive+no_connect"))
    )
    (net (code "133") (name "unconnected-(CN1001-Pad62)") (class "Default")
      (node (ref "CN1001") (pin "62") (pinfunction "62_62") (pintype "passive"))
    )
    (net (code "134") (name "unconnected-(CN1001-Pad66)") (class "Default")
      (node (ref "CN1001") (pin "66") (pinfunction "66_66") (pintype "passive"))
    )
    (net (code "135") (name "unconnected-(CN1001-Pad77)") (class "Default")
      (node (ref "CN1001") (pin "77") (pinfunction "77_77") (pintype "passive"))
    )
    (net (code "136") (name "unconnected-(CN1001-Pad81)") (class "Default")
      (node (ref "CN1001") (pin "81") (pinfunction "81_81") (pintype "passive"))
    )
    (net (code "137") (name "unconnected-(CN1001-Pad85)") (class "Default")
      (node (ref "CN1001") (pin "85") (pinfunction "85_85") (pintype "passive"))
    )
    (net (code "138") (name "unconnected-(CN1001-Pad89)") (class "Default")
      (node (ref "CN1001") (pin "89") (pinfunction "89_89") (pintype "passive"))
    )
    (net (code "139") (name "unconnected-(CN1001-Pad93)") (class "Default")
      (node (ref "CN1001") (pin "93") (pinfunction "93_93") (pintype "passive"))
    )
    (net (code "140") (name "unconnected-(CN1001-Pad94)") (class "Default")
      (node (ref "CN1001") (pin "94") (pinfunction "94_94") (pintype "passive"))
    )
    (net (code "141") (name "unconnected-(CN1001-Pad97)") (class "Default")
      (node (ref "CN1001") (pin "97") (pinfunction "97_97") (pintype "passive"))
    )
    (net (code "142") (name "unconnected-(CN1001-Pad98)") (class "Default")
      (node (ref "CN1001") (pin "98") (pinfunction "98_98") (pintype "passive"))
    )
  )
)
